# Messsystem.net
KiCad netlist of a schematic drawn in Altium Designer
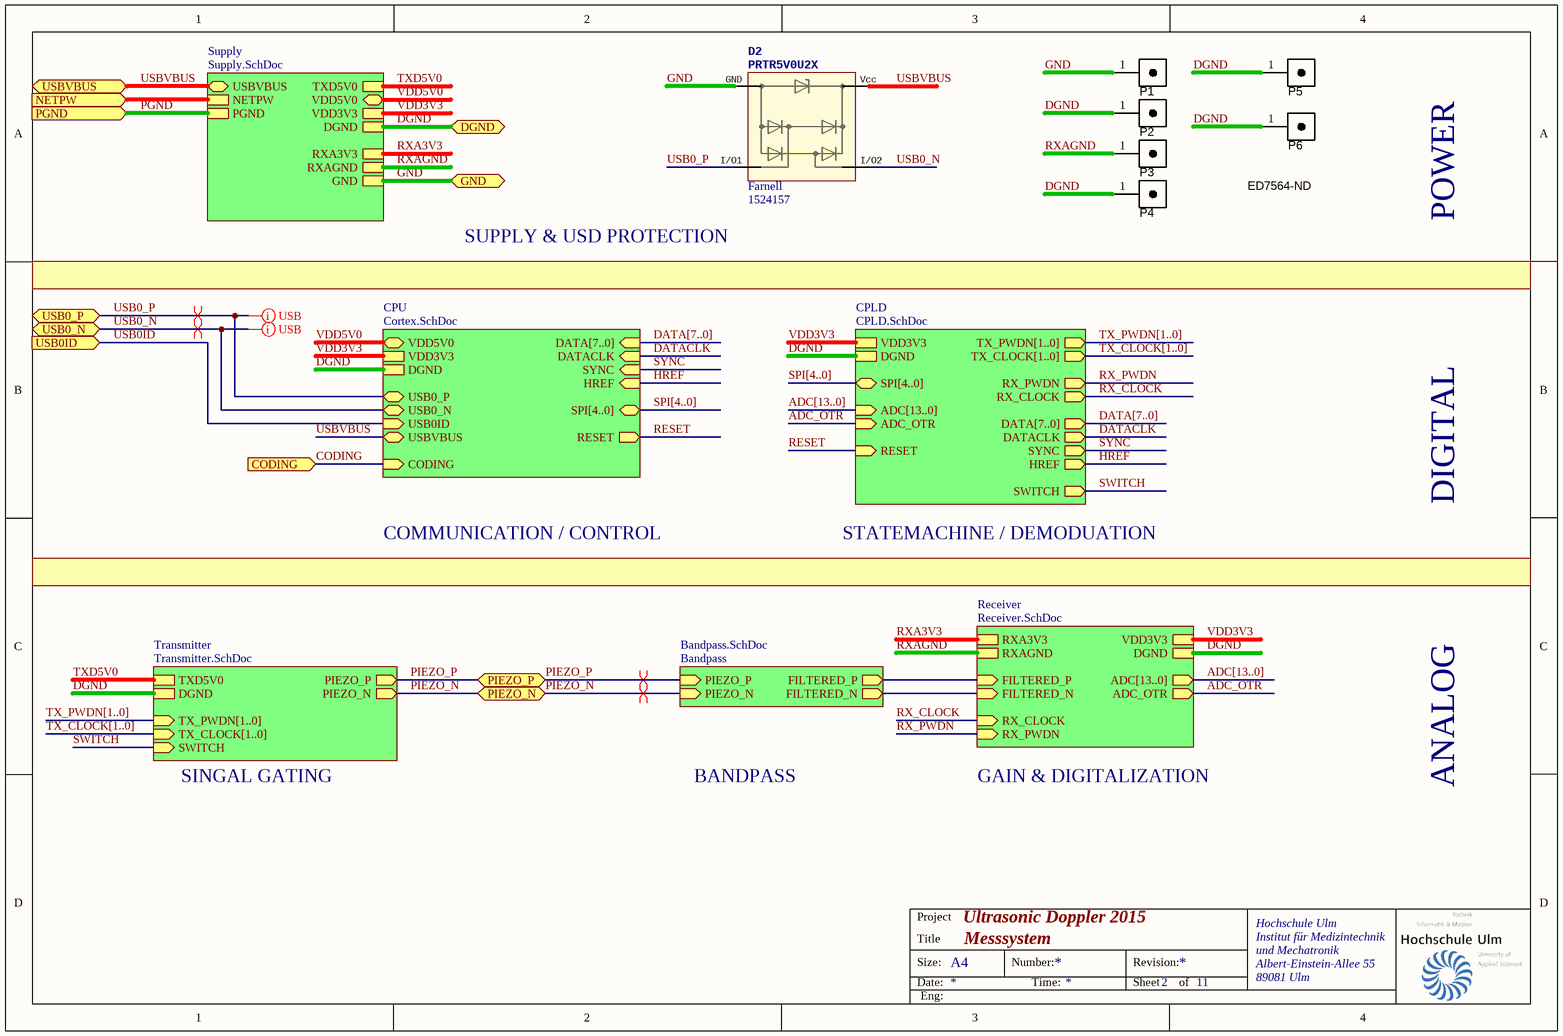
[diagram p0: Messsystem.SchDoc]

(export (version "E")
  (design (tool "Eeschema 10.0.6"))
  (components
    (comp (ref "D2")
      (value "PRTR5V0U2X")
      (footprint "SOT143-B")
      (description "rail-to-rail ESD protection diode")
      (fields (field (name "SUPPLIER 1") "Farnell") (field (name "SUPPLIER PART NUMBER 1") "1524157"))
      (libsource (lib "USD Parts") (part "PRTR5V0"))
    )
    (comp (ref "P1")
      (value "CONN_HEADER_PLUG_1x1P_0.100in")
      (footprint "1x1POS_HEADER_LOWPROF")
      (description "Pin header for socket THT 1-Pos Low profile Single-row 2.54mm pitch")
      (libsource (lib "USD Parts") (part "CONN_HEADER_PLUG_1x1P_0.100in"))
    )
    (comp (ref "P2")
      (value "CONN_HEADER_PLUG_1x1P_0.100in")
      (footprint "1x1POS_HEADER_LOWPROF")
      (description "Pin header for socket THT 1-Pos Low profile Single-row 2.54mm pitch")
      (libsource (lib "USD Parts") (part "CONN_HEADER_PLUG_1x1P_0.100in"))
    )
    (comp (ref "P3")
      (value "CONN_HEADER_PLUG_1x1P_0.100in")
      (footprint "1x1POS_HEADER_LOWPROF")
      (description "Pin header for socket THT 1-Pos Low profile Single-row 2.54mm pitch")
      (libsource (lib "USD Parts") (part "CONN_HEADER_PLUG_1x1P_0.100in"))
    )
    (comp (ref "P4")
      (value "CONN_HEADER_PLUG_1x1P_0.100in")
      (footprint "1x1POS_HEADER_LOWPROF")
      (description "Pin header for socket THT 1-Pos Low profile Single-row 2.54mm pitch")
      (fields (field (name "SUPPLIER PART NUMBER 1") "ED7564-ND"))
      (libsource (lib "USD Parts") (part "CONN_HEADER_PLUG_1x1P_0.100in"))
    )
    (comp (ref "P5")
      (value "CONN_HEADER_PLUG_1x1P_0.100in")
      (footprint "1x1POS_HEADER_LOWPROF")
      (description "Pin header for socket THT 1-Pos Low profile Single-row 2.54mm pitch")
      (libsource (lib "USD Parts") (part "CONN_HEADER_PLUG_1x1P_0.100in"))
    )
    (comp (ref "P6")
      (value "CONN_HEADER_PLUG_1x1P_0.100in")
      (footprint "1x1POS_HEADER_LOWPROF")
      (description "Pin header for socket THT 1-Pos Low profile Single-row 2.54mm pitch")
      (libsource (lib "USD Parts") (part "CONN_HEADER_PLUG_1x1P_0.100in"))
    )
  )
  (nets
    (net (code "37") (name "/DGND") (class "Default")
      (node (ref "P2") (pin "1") (pinfunction "1_1") (pintype "passive"))
      (node (ref "P4") (pin "1") (pinfunction "1_1") (pintype "passive"))
      (node (ref "P5") (pin "1") (pinfunction "1_1") (pintype "passive"))
      (node (ref "P6") (pin "1") (pinfunction "1_1") (pintype "passive"))
    )
    (net (code "40") (name "/GND") (class "Default")
      (node (ref "D2") (pin "GND") (pinfunction "1_GND") (pintype "passive"))
      (node (ref "P1") (pin "1") (pinfunction "1_1") (pintype "passive"))
    )
    (net (code "48") (name "/RXAGND") (class "Default")
      (node (ref "P3") (pin "1") (pinfunction "1_1") (pintype "passive"))
    )
    (net (code "58") (name "/USB0_N") (class "Default")
      (node (ref "D2") (pin "I/O2") (pinfunction "3_I/O2") (pintype "passive"))
    )
    (net (code "59") (name "/USB0_P") (class "Default")
      (node (ref "D2") (pin "I/O1") (pinfunction "2_I/O1") (pintype "passive"))
    )
    (net (code "60") (name "/USBVBUS") (class "Default")
      (node (ref "D2") (pin "Vcc") (pinfunction "3_Vcc") (pintype "passive"))
    )
  )
)
